# BMS1.net
KiCad netlist of a schematic drawn in Altium Designer
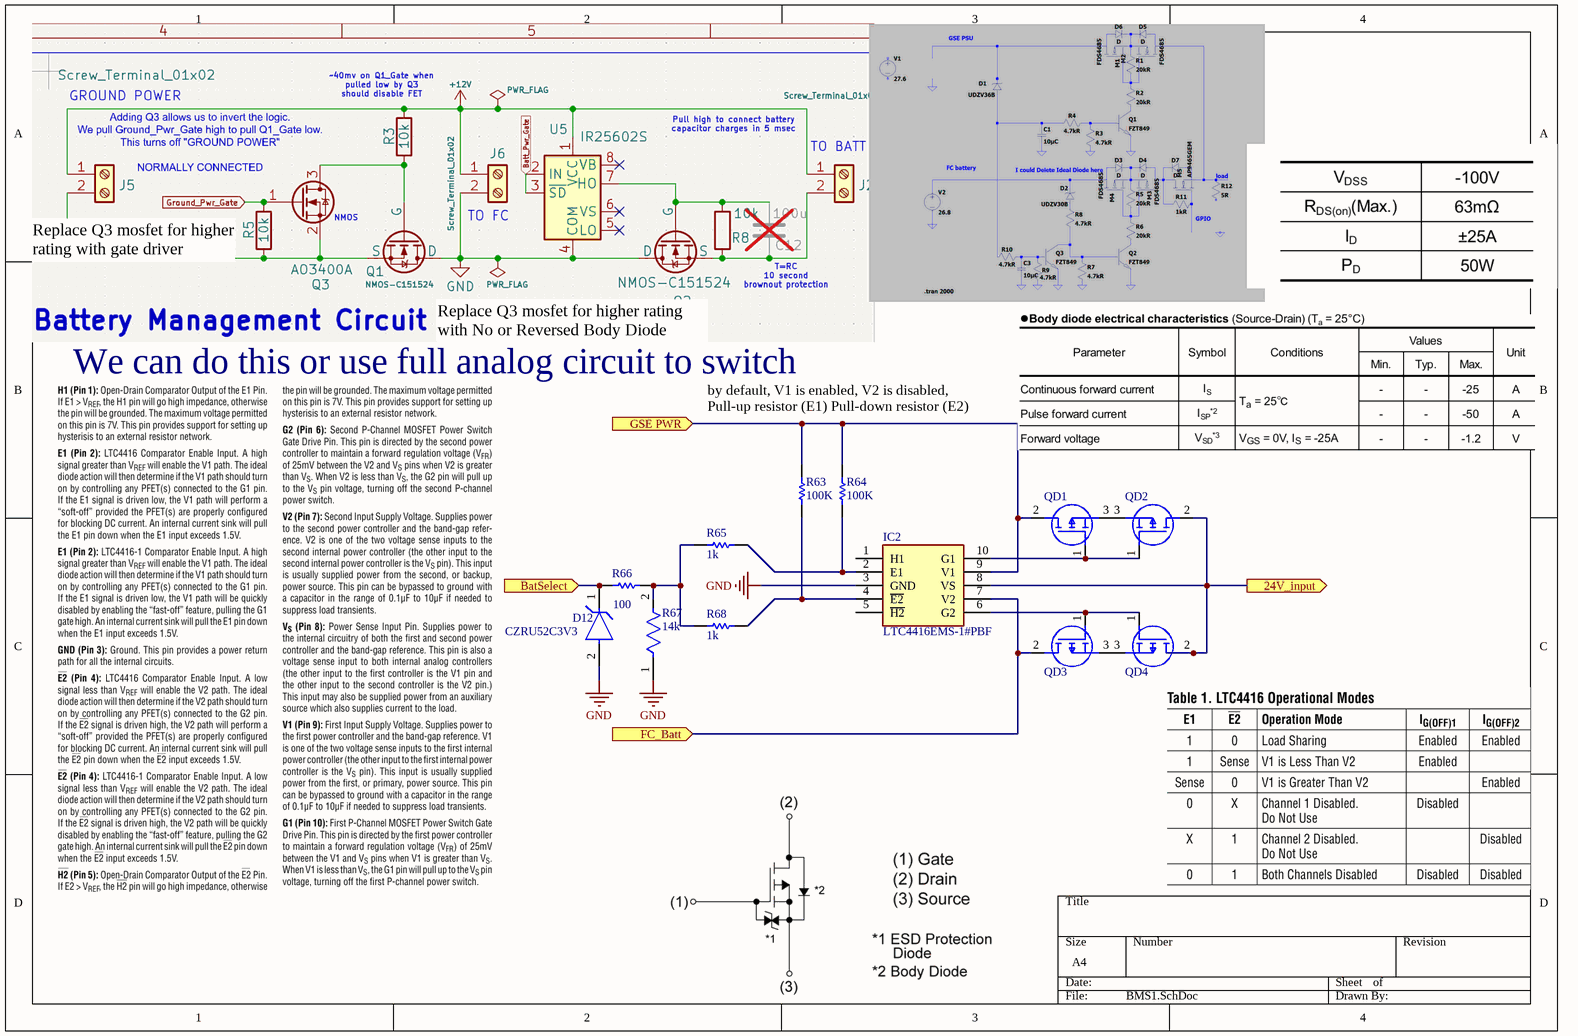
[diagram p0: BMS1.SchDoc]

(export (version "E")
  (design (tool "Eeschema 10.0.6"))
  (components
    (comp (ref "D12")
      (value "CZRU52C3V3")
      (footprint "FP-0603-SOD-523F-MFG")
      (description "DIODE ZENER 3.3V 150MW 0603")
      (fields (field (name "TOLERANCE") "5%"))
      (libsource (lib "Altium Content Vault") (part "f813f71cba58e380607f5dd3caf9714"))
    )
    (comp (ref "IC2")
      (value "LTC4416EMS-1#PBF")
      (footprint "SamacSys:SOP50P490X110-10N")
      (description "Integrated Circuit")
      (fields (field (name "MOUSER PART NUMBER") "584-LTC4416EMS-1#PBF"))
      (libsource (lib "*") (part "LTC4416EMS-1#PBF"))
    )
    (comp (ref "QD1")
      (value "~")
      (footprint "SamacSys:R6024KNJTL")
      (description "MOSFET (P-Channel) RSJ250P10FRATL")
      (fields
        (field (name "MANUFACTURER_PART_NUMBER") "RSJ250P10FRATL")
        (field (name "MOUSER PART NUMBER") "755-RSJ250P10FRATL")
      )
      (libsource (lib "*") (part "RSJ250P10FRATL"))
    )
    (comp (ref "QD2")
      (value "~")
      (footprint "SamacSys:R6024KNJTL")
      (description "MOSFET (P-Channel) RSJ250P10FRATL")
      (fields
        (field (name "MANUFACTURER_PART_NUMBER") "RSJ250P10FRATL")
        (field (name "MOUSER PART NUMBER") "755-RSJ250P10FRATL")
      )
      (libsource (lib "*") (part "RSJ250P10FRATL"))
    )
    (comp (ref "QD3")
      (value "~")
      (footprint "SamacSys:R6024KNJTL")
      (description "MOSFET (P-Channel) RSJ250P10FRATL")
      (fields
        (field (name "MANUFACTURER_PART_NUMBER") "RSJ250P10FRATL")
        (field (name "MOUSER PART NUMBER") "755-RSJ250P10FRATL")
      )
      (libsource (lib "*") (part "RSJ250P10FRATL"))
    )
    (comp (ref "QD4")
      (value "~")
      (footprint "SamacSys:R6024KNJTL")
      (description "MOSFET (P-Channel) RSJ250P10FRATL")
      (fields
        (field (name "MANUFACTURER_PART_NUMBER") "RSJ250P10FRATL")
        (field (name "MOUSER PART NUMBER") "755-RSJ250P10FRATL")
      )
      (libsource (lib "*") (part "RSJ250P10FRATL"))
    )
    (comp (ref "R63")
      (value "100K")
      (footprint "RESC1609X55X30ML10T20")
      (description "RES 100K OHM 0.1% 1/10W 0603")
      (fields (field (name "MANUFACTURER") "Vishay Dale") (field (name "PART NUMBER") "TNPW0603100KBETA"))
      (libsource (lib "Altium Content Vault") (part "RES"))
    )
    (comp (ref "R64")
      (value "100K")
      (footprint "RESC1609X55X30ML10T20")
      (description "RES 100K OHM 0.1% 1/10W 0603")
      (fields (field (name "MANUFACTURER") "Vishay Dale") (field (name "PART NUMBER") "TNPW0603100KBETA"))
      (libsource (lib "Altium Content Vault") (part "RES"))
    )
    (comp (ref "R65")
      (value "1k")
      (footprint "RESC2013X60X35ML10T20")
      (description "Chip Resistor, 1 KOhm, +/- 1%, 125 mW, -55 to 155 degC, 0805 (2012 Metric), RoHS, Tape and Reel")
      (fields (field (name "TOLERANCE") "1%") (field (name "MANUFACTURER") "Yageo"))
      (libsource (lib "Altium Content Vault") (part "RES-2"))
    )
    (comp (ref "R66")
      (value "100")
      (footprint "RESC1608X55X30LL15T15")
      (fields (field (name "MANUFACTURER") "Panasonic") (field (name "PART NUMBER") "ERJ-3EKF1000V"))
      (libsource (lib "Altium Content Vault") (part "RES"))
    )
    (comp (ref "R67")
      (value "14k")
      (footprint "FP-CRCW0603-e3-IPC_B")
      (description "RES Thick Film, 14kΩ, 1%, 0.1W, 100ppm/°C, 0603")
      (fields (field (name "TOLERANCE") "1%"))
      (libsource (lib "Altium Content Vault") (part "1029c3af85768c4190bb7ad29bc67b5"))
    )
    (comp (ref "R68")
      (value "1k")
      (footprint "RESC2013X60X35ML10T20")
      (description "Chip Resistor, 1 KOhm, +/- 1%, 125 mW, -55 to 155 degC, 0805 (2012 Metric), RoHS, Tape and Reel")
      (fields (field (name "TOLERANCE") "1%") (field (name "MANUFACTURER") "Yageo"))
      (libsource (lib "Altium Content Vault") (part "RES-2"))
    )
  )
  (nets
    (net (code "1") (name "/24V_input") (class "Default")
      (node (ref "IC2") (pin "8") (pinfunction "VS_8") (pintype "passive"))
      (node (ref "QD2") (pin "2") (pinfunction "D_2") (pintype "passive"))
      (node (ref "QD4") (pin "2") (pinfunction "D_2") (pintype "passive"))
    )
    (net (code "2") (name "/BatSelect") (class "Default")
      (node (ref "D12") (pin "1") (pinfunction "C_1") (pintype "passive"))
      (node (ref "R66") (pin "1") (pinfunction "1_1") (pintype "passive"))
    )
    (net (code "3") (name "/FC_Batt") (class "Default")
      (node (ref "IC2") (pin "7") (pinfunction "V2_7") (pintype "passive"))
      (node (ref "QD3") (pin "2") (pinfunction "D_2") (pintype "passive"))
    )
    (net (code "4") (name "/GSE PWR") (class "Default")
      (node (ref "IC2") (pin "9") (pinfunction "V1_9") (pintype "passive"))
      (node (ref "QD1") (pin "2") (pinfunction "D_2") (pintype "passive"))
      (node (ref "R63") (pin "2") (pinfunction "2_2") (pintype "passive"))
      (node (ref "R64") (pin "2") (pinfunction "2_2") (pintype "passive"))
    )
    (net (code "5") (name "GND") (class "Default")
      (node (ref "D12") (pin "2") (pinfunction "A_2") (pintype "passive"))
      (node (ref "IC2") (pin "3") (pinfunction "GND_3") (pintype "passive"))
      (node (ref "R67") (pin "1") (pinfunction "1_1") (pintype "passive"))
    )
    (net (code "6") (name "Net-(IC2-E1)") (class "Default")
      (node (ref "IC2") (pin "2") (pinfunction "E1_2") (pintype "passive"))
      (node (ref "R64") (pin "1") (pinfunction "1_1") (pintype "passive"))
      (node (ref "R65") (pin "2") (pinfunction "2_2") (pintype "passive"))
    )
    (net (code "7") (name "Net-(IC2-G1)") (class "Default")
      (node (ref "IC2") (pin "10") (pinfunction "G1_10") (pintype "passive"))
      (node (ref "QD1") (pin "1") (pinfunction "G_1") (pintype "passive"))
      (node (ref "QD2") (pin "1") (pinfunction "G_1") (pintype "passive"))
    )
    (net (code "8") (name "Net-(IC2-G2)") (class "Default")
      (node (ref "IC2") (pin "6") (pinfunction "G2_6") (pintype "passive"))
      (node (ref "QD3") (pin "1") (pinfunction "G_1") (pintype "passive"))
      (node (ref "QD4") (pin "1") (pinfunction "G_1") (pintype "passive"))
    )
    (net (code "9") (name "Net-(IC2-~{E2})") (class "Default")
      (node (ref "IC2") (pin "4") (pinfunction "~{E2}_4") (pintype "passive"))
      (node (ref "R63") (pin "1") (pinfunction "1_1") (pintype "passive"))
      (node (ref "R68") (pin "2") (pinfunction "2_2") (pintype "passive"))
    )
    (net (code "10") (name "Net-(QD1-S)") (class "Default")
      (node (ref "QD1") (pin "3") (pinfunction "S_3") (pintype "passive"))
      (node (ref "QD2") (pin "3") (pinfunction "S_3") (pintype "passive"))
    )
    (net (code "11") (name "Net-(QD3-S)") (class "Default")
      (node (ref "QD3") (pin "3") (pinfunction "S_3") (pintype "passive"))
      (node (ref "QD4") (pin "3") (pinfunction "S_3") (pintype "passive"))
    )
    (net (code "12") (name "Net-(R65-Pad1)") (class "Default")
      (node (ref "R65") (pin "1") (pinfunction "1_1") (pintype "passive"))
      (node (ref "R66") (pin "2") (pinfunction "2_2") (pintype "passive"))
      (node (ref "R67") (pin "2") (pinfunction "2_2") (pintype "passive"))
      (node (ref "R68") (pin "1") (pinfunction "1_1") (pintype "passive"))
    )
    (net (code "13") (name "unconnected-(IC2-H1-Pad1)") (class "Default")
      (node (ref "IC2") (pin "1") (pinfunction "H1_1") (pintype "passive"))
    )
    (net (code "14") (name "unconnected-(IC2-~{H2}-Pad5)") (class "Default")
      (node (ref "IC2") (pin "5") (pinfunction "~{H2}_5") (pintype "passive"))
    )
  )
)
